# light.net
KiCad netlist of a schematic drawn in EAGLE
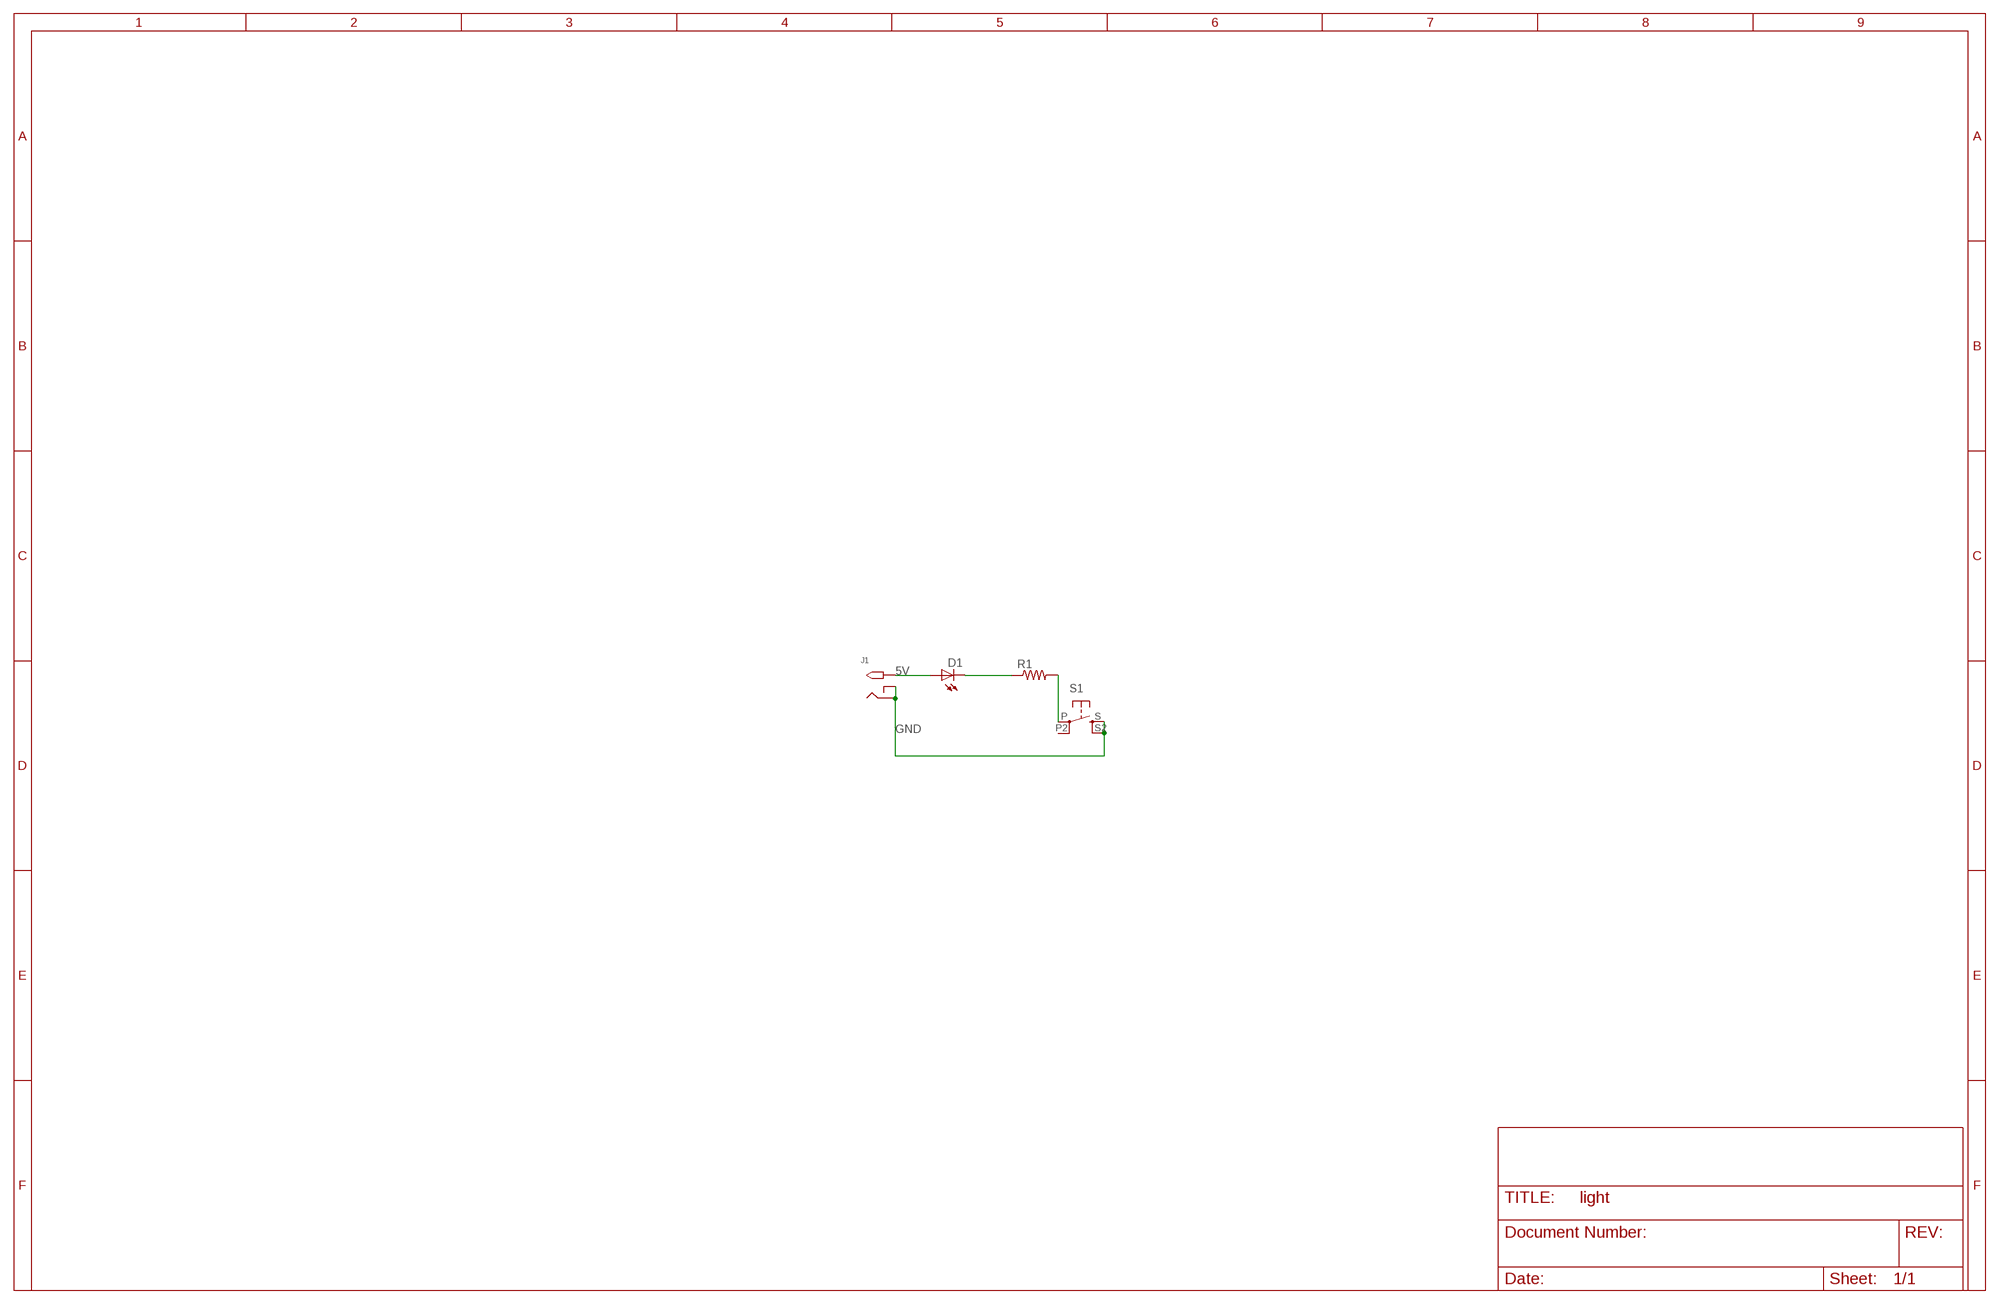
[diagram p0: schematic, sheet 1]

(export (version "E")
  (design (tool "Eeschema 10.0.6"))
  (components
    (comp (ref "D1")
      (value "LED5MM")
      (footprint "eagle-import:LED5MM")
      (fields (field (name "CREATOR") "Swanson") (field (name "REVIEWER") "Swanson"))
      (libsource (lib "eagle-import") (part "LED5MM"))
    )
    (comp (ref "J1")
      (value "2.1MMJACKTHM")
      (footprint "eagle-import:PJ-102A")
      (fields (field (name "CREATOR") "Swanson") (field (name "REVIEWER") "Swanson"))
      (libsource (lib "eagle-import") (part "2.1MMJACKTHM"))
    )
    (comp (ref "R1")
      (value "RESISTORTH-1/4W-CARBON")
      (footprint "eagle-import:RESAD1160W55L680D260_HS")
      (fields (field (name "CREATOR") "Swanson") (field (name "REVIEWER") "Swanson"))
      (libsource (lib "eagle-import") (part "RESISTORTH-1/4W-CARBON"))
    )
    (comp (ref "S1")
      (value "PUSH-BUTTON-SQUARE")
      (footprint "eagle-import:BUTTON-TACTILE-SQUARE-ADAFRUIT1010")
      (fields (field (name "CREATOR") "Swanson") (field (name "REVIEWER") "Swanson"))
      (libsource (lib "eagle-import") (part "PUSH-BUTTON-SQUARE"))
    )
  )
  (nets
    (net (code "1") (name "/5V") (class "Default")
      (node (ref "D1") (pin "A") (pinfunction "A_A") (pintype "passive"))
      (node (ref "J1") (pin "TIP") (pinfunction "TIP_TIP") (pintype "bidirectional"))
    )
    (net (code "2") (name "/GND") (class "Default")
      (node (ref "J1") (pin "RING") (pinfunction "RING_RING") (pintype "bidirectional"))
      (node (ref "J1") (pin "RING_SW") (pinfunction "RING_SW_RING_SW") (pintype "bidirectional"))
      (node (ref "S1") (pin "S") (pinfunction "S_S") (pintype "passive"))
      (node (ref "S1") (pin "S2") (pinfunction "S1_S2") (pintype "passive"))
    )
    (net (code "3") (name "Net-(D1-C)") (class "Default")
      (node (ref "D1") (pin "K") (pinfunction "C_K") (pintype "passive"))
      (node (ref "R1") (pin "1") (pinfunction "1_1") (pintype "passive"))
    )
    (net (code "4") (name "Net-(R1-Pad2)") (class "Default")
      (node (ref "R1") (pin "2") (pinfunction "2_2") (pintype "passive"))
      (node (ref "S1") (pin "P") (pinfunction "P_P") (pintype "passive"))
    )
    (net (code "5") (name "unconnected-(S1-P1-PadP2)") (class "Default")
      (node (ref "S1") (pin "P2") (pinfunction "P1_P2") (pintype "passive"))
    )
  )
)
